# BMI270-Accelerometer-Gyroscope.net
KiCad netlist of a schematic drawn in Altium Designer
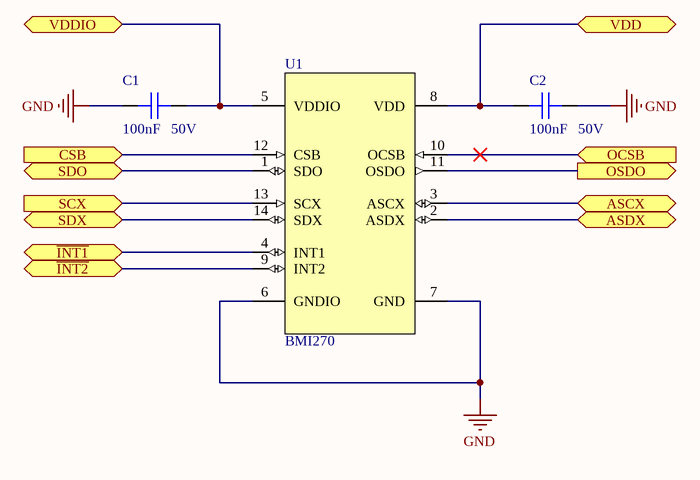
[diagram p0: BMI270-Accelerometer-Gyroscope.SchDoc]

(export (version "E")
  (design (tool "Eeschema 10.0.6"))
  (components
    (comp (ref "C1")
      (value "CAP CER 0.1UF 50V X7R 0402")
      (footprint "C0402")
      (description "0.1µF ±10% 50V Ceramic Capacitor X7R 0402 (1005 Metric)")
      (fields
        (field (name "MANUFACTURER PART NUMBER") "CGA2B3X7R1H104K050BB")
        (field (name "MANUFACTURER") "TDK")
        (field (name "CAPACITANCE") "100nF")
        (field (name "VOLTAGE") "50V")
      )
      (libsource (lib "capacitors_smd") (part "CAP CER 0.1UF 50V X7R 0402"))
    )
    (comp (ref "C2")
      (value "CAP CER 0.1UF 50V X7R 0402")
      (footprint "C0402")
      (description "0.1µF ±10% 50V Ceramic Capacitor X7R 0402 (1005 Metric)")
      (fields
        (field (name "MANUFACTURER PART NUMBER") "CGA2B3X7R1H104K050BB")
        (field (name "MANUFACTURER") "TDK")
        (field (name "CAPACITANCE") "100nF")
        (field (name "VOLTAGE") "50V")
      )
      (libsource (lib "capacitors_smd") (part "CAP CER 0.1UF 50V X7R 0402"))
    )
    (comp (ref "U1")
      (value "BMI270")
      (footprint "XDCR_BMI270")
      (description "Accelerometer, Gyroscope, 6 Axis Sensor I²C, SPI Output")
      (fields (field (name "MANUFACTURER") "Bosch Sensortec"))
      (libsource (lib "BLDC_Motor_Driver") (part "IC BMI270 IMU ACCEL/GYRO I2C/SPI 14LGA"))
    )
  )
  (nets
    (net (code "1") (name "/ASCX") (class "Default")
      (node (ref "U1") (pin "3") (pinfunction "ASCX_3") (pintype "bidirectional"))
    )
    (net (code "2") (name "/ASDX") (class "Default")
      (node (ref "U1") (pin "2") (pinfunction "ASDX_2") (pintype "bidirectional"))
    )
    (net (code "3") (name "/CSB") (class "Default")
      (node (ref "U1") (pin "12") (pinfunction "CSB_12") (pintype "input"))
    )
    (net (code "4") (name "/INT1") (class "Default")
      (node (ref "U1") (pin "4") (pinfunction "INT1_4") (pintype "bidirectional"))
    )
    (net (code "5") (name "/INT2") (class "Default")
      (node (ref "U1") (pin "9") (pinfunction "INT2_9") (pintype "bidirectional"))
    )
    (net (code "6") (name "/OCSB") (class "Default")
      (node (ref "U1") (pin "10") (pinfunction "OCSB_10") (pintype "input"))
    )
    (net (code "7") (name "/OSDO") (class "Default")
      (node (ref "U1") (pin "11") (pinfunction "OSDO_11") (pintype "output"))
    )
    (net (code "8") (name "/SCX") (class "Default")
      (node (ref "U1") (pin "13") (pinfunction "SCX_13") (pintype "input"))
    )
    (net (code "9") (name "/SDO") (class "Default")
      (node (ref "U1") (pin "1") (pinfunction "SDO_1") (pintype "bidirectional"))
    )
    (net (code "10") (name "/SDX") (class "Default")
      (node (ref "U1") (pin "14") (pinfunction "SDX_14") (pintype "bidirectional"))
    )
    (net (code "11") (name "/VDD") (class "Default")
      (node (ref "C2") (pin "1") (pinfunction "1_1") (pintype "passive"))
      (node (ref "U1") (pin "8") (pinfunction "VDD_8") (pintype "power_in"))
    )
    (net (code "12") (name "/VDDIO") (class "Default")
      (node (ref "C1") (pin "2") (pinfunction "2_2") (pintype "passive"))
      (node (ref "U1") (pin "5") (pinfunction "VDDIO_5") (pintype "power_in"))
    )
    (net (code "13") (name "GND") (class "Default")
      (node (ref "C1") (pin "1") (pinfunction "1_1") (pintype "passive"))
      (node (ref "C2") (pin "2") (pinfunction "2_2") (pintype "passive"))
      (node (ref "U1") (pin "6") (pinfunction "GNDIO_6") (pintype "power_in"))
      (node (ref "U1") (pin "7") (pinfunction "GND_7") (pintype "power_in"))
    )
  )
)
